# 3_2___TFT_IPS_320x480.net
KiCad netlist of a schematic drawn in Altium Designer
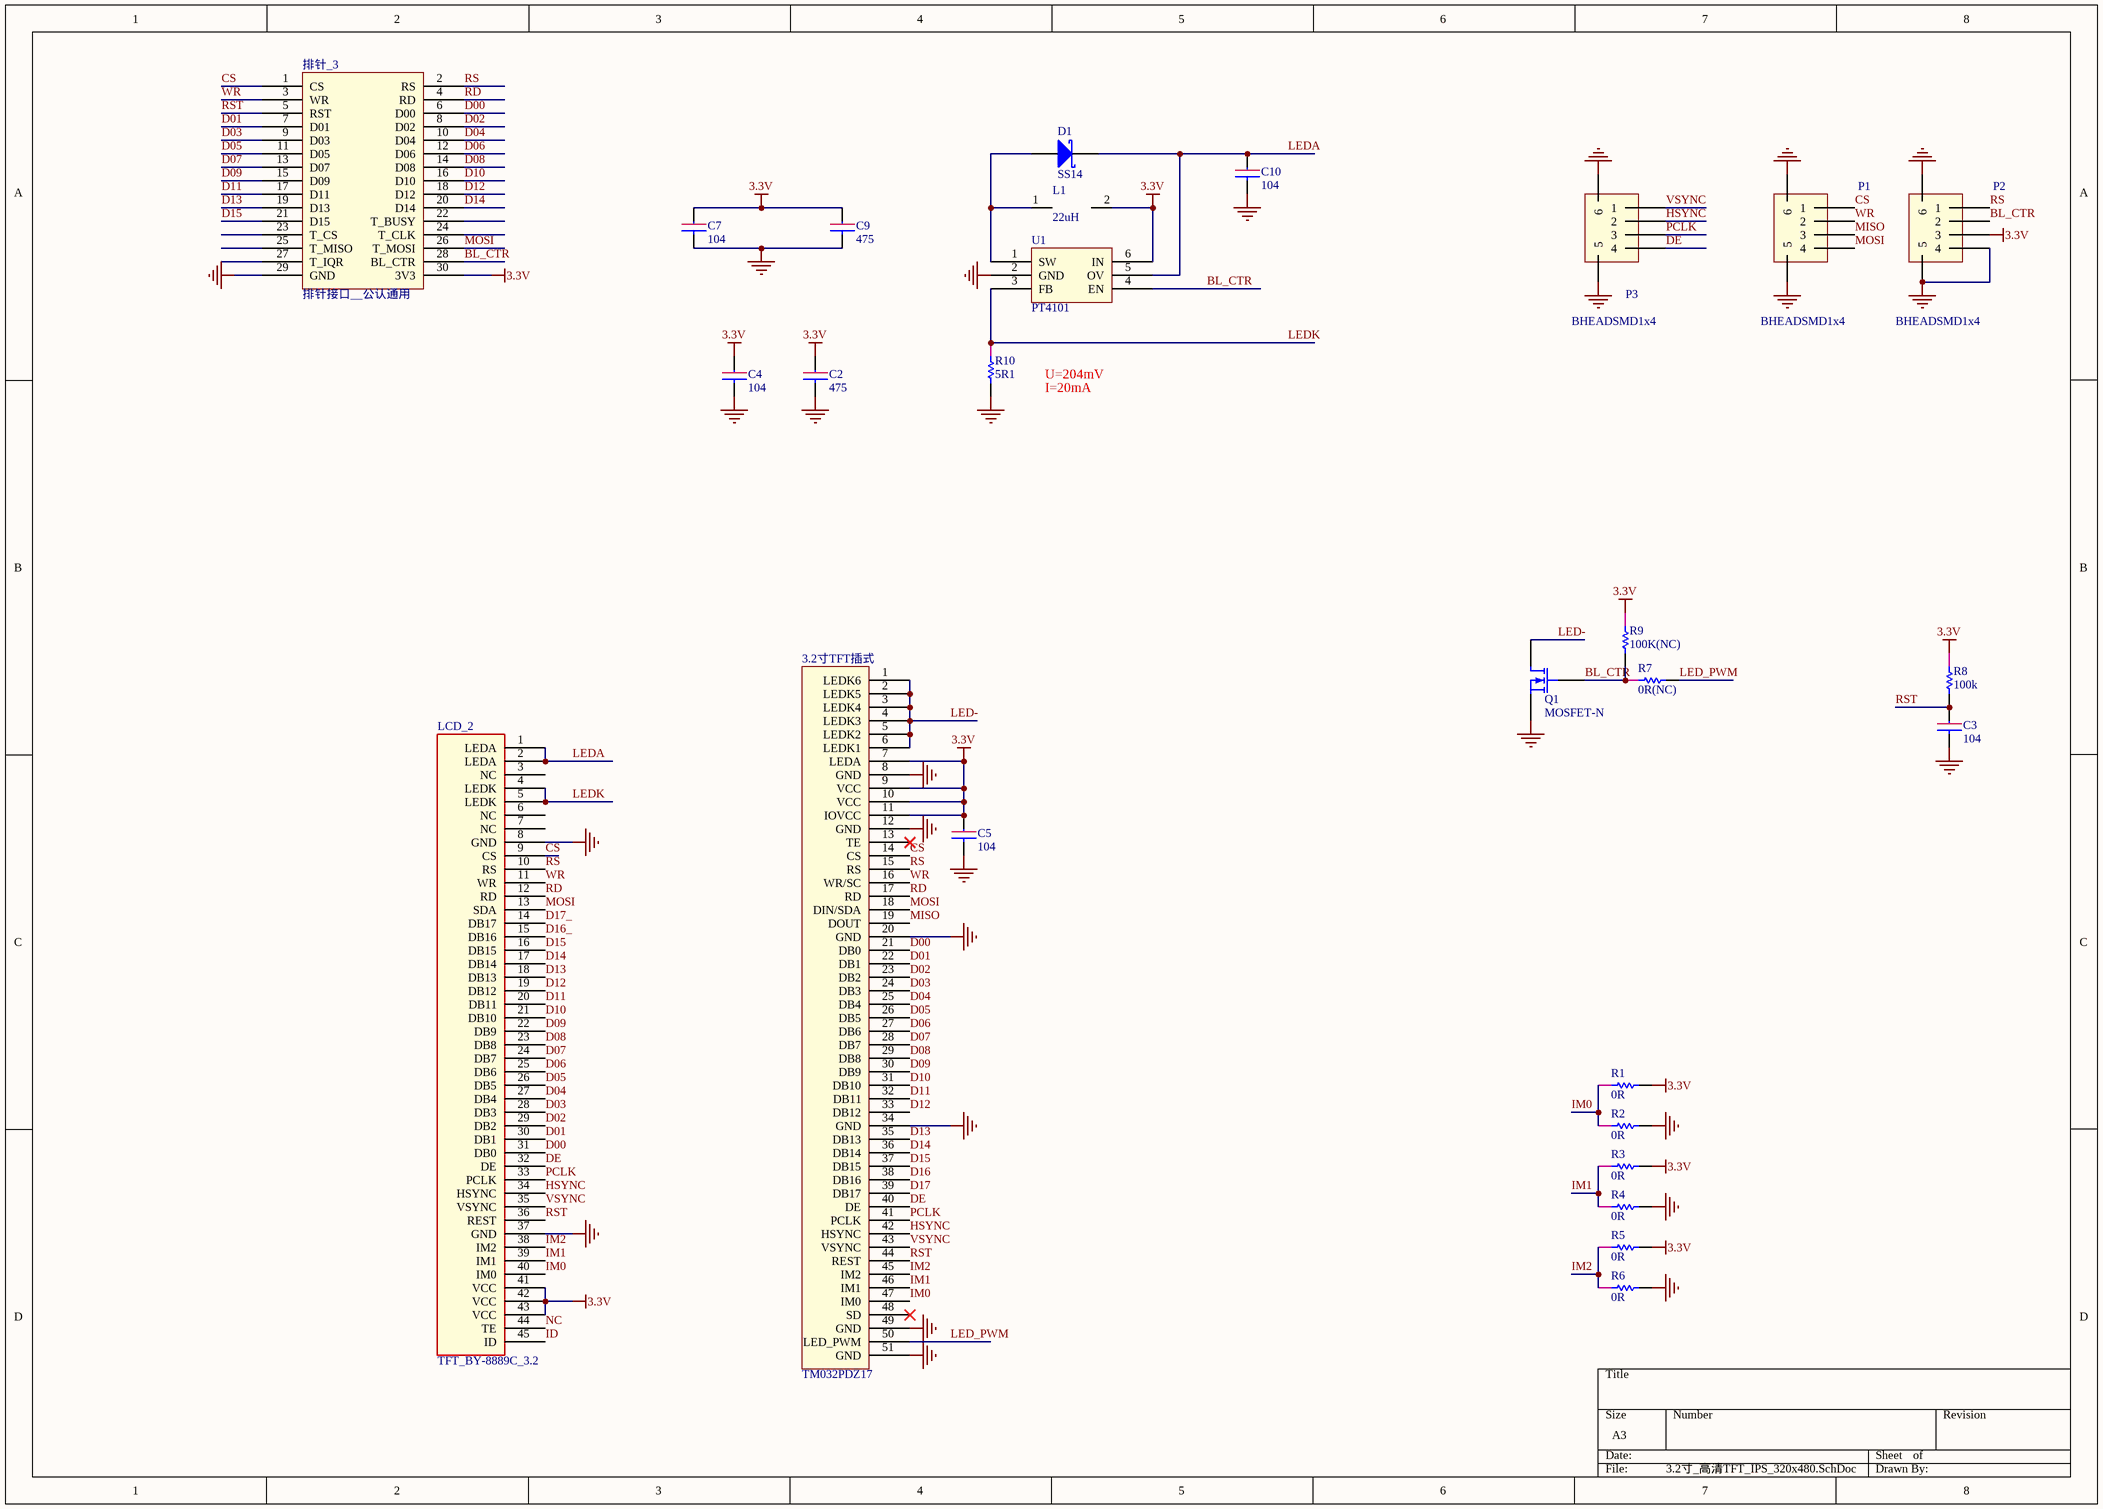
[diagram p0: 3.2寸_高清TFT_IPS_320x480.SchDoc]

(export (version "E")
  (design (tool "Eeschema 10.0.6"))
  (components
    (comp (ref "3.2寸TFT插式")
      (value "TM032PDZ17")
      (footprint "TM032PDZ17")
      (libsource (lib "Tiky") (part "TM032PDZ17"))
    )
    (comp (ref "C2") (value "475") (footprint "C0603-2") (libsource (lib "Tiky") (part "cap")))
    (comp (ref "C3") (value "104") (footprint "C0603-1") (libsource (lib "Tiky") (part "cap")))
    (comp (ref "C4") (value "104") (footprint "C0603-1") (libsource (lib "Tiky") (part "cap")))
    (comp (ref "C5") (value "104") (footprint "C0603-1") (libsource (lib "Tiky") (part "cap")))
    (comp (ref "C7") (value "104") (footprint "C0603-1") (libsource (lib "Tiky") (part "cap")))
    (comp (ref "C9") (value "475") (footprint "C0603-2") (libsource (lib "Tiky") (part "cap")))
    (comp (ref "C10") (value "104") (footprint "C0603-2") (libsource (lib "Tiky") (part "cap")))
    (comp (ref "D1")
      (value "SS14")
      (footprint "SOD123")
      (description "Schottky Diode")
      (fields (field (name "PUBLISHER") "Altium Limited"))
      (libsource (lib "Miscellaneous Devices") (part "D Schottky"))
    )
    (comp (ref "L1") (value "22uH") (footprint "L1206") (libsource (lib "Tiky") (part "Inductor")))
    (comp (ref "LCD_2")
      (value "TFT_BY-8889C_3.2")
      (footprint "TM032PDZ13")
      (libsource (lib "Tiky") (part "TFT_BY-8889C_3.2"))
    )
    (comp (ref "P1")
      (value "BHEADSMD1x4")
      (footprint "BHEADSMD1x4")
      (libsource (lib "Tiky") (part "BHEADSMD1x4"))
    )
    (comp (ref "P2")
      (value "BHEADSMD1x4")
      (footprint "BHEADSMD1x4")
      (libsource (lib "Tiky") (part "BHEADSMD1x4"))
    )
    (comp (ref "P3")
      (value "BHEADSMD1x4")
      (footprint "BHEADSMD1x4")
      (libsource (lib "Tiky") (part "BHEADSMD1x4"))
    )
    (comp (ref "Q1") (value "MOSFET-N") (footprint "SOT23A") (libsource (lib "Tiky") (part "MOSFET-N")))
    (comp (ref "R1") (value "0R") (footprint "R0603") (libsource (lib "Tiky") (part "Resistor")))
    (comp (ref "R2") (value "0R") (footprint "R0603") (libsource (lib "Tiky") (part "Resistor")))
    (comp (ref "R3") (value "0R") (footprint "R0603") (libsource (lib "Tiky") (part "Resistor")))
    (comp (ref "R4") (value "0R") (footprint "R0603") (libsource (lib "Tiky") (part "Resistor")))
    (comp (ref "R5") (value "0R") (footprint "R0603") (libsource (lib "Tiky") (part "Resistor")))
    (comp (ref "R6") (value "0R") (footprint "R0603") (libsource (lib "Tiky") (part "Resistor")))
    (comp (ref "R7") (value "0R(NC)") (footprint "R0603") (libsource (lib "Tiky") (part "Resistor")))
    (comp (ref "R8") (value "100k") (footprint "R0603") (libsource (lib "Tiky") (part "Resistor")))
    (comp (ref "R9") (value "100K(NC)") (footprint "R0603") (libsource (lib "Tiky") (part "Resistor")))
    (comp (ref "R10") (value "5R1") (footprint "R0603") (libsource (lib "Tiky") (part "Resistor")))
    (comp (ref "U1") (value "PT4101") (footprint "SOT23-6") (libsource (lib "Tiky") (part "PT4101")))
    (comp (ref "排针_3")
      (value "排针接口__公认通用")
      (footprint "P_Head_2x15")
      (libsource (lib "Tiky") (part "LCD_common"))
    )
  )
  (nets
    (net (code "1") (name "/BL_CTR") (class "Default")
      (node (ref "P2") (pin "2") (pinfunction "2_2") (pintype "passive"))
      (node (ref "Q1") (pin "1") (pinfunction "G_1") (pintype "passive"))
      (node (ref "R7") (pin "1") (pinfunction "1_1") (pintype "passive"))
      (node (ref "R9") (pin "2") (pinfunction "2_2") (pintype "passive"))
      (node (ref "U1") (pin "4") (pinfunction "EN_4") (pintype "passive"))
      (node (ref "排针_3") (pin "28") (pinfunction "BL_CTR_28") (pintype "passive"))
    )
    (net (code "2") (name "/CS") (class "Default")
      (node (ref "3.2寸TFT插式") (pin "14") (pinfunction "CS_14") (pintype "passive"))
      (node (ref "LCD_2") (pin "9") (pinfunction "CS_9") (pintype "passive"))
      (node (ref "P1") (pin "1") (pinfunction "1_1") (pintype "passive"))
      (node (ref "排针_3") (pin "1") (pinfunction "CS_1") (pintype "passive"))
    )
    (net (code "3") (name "/D00") (class "Default")
      (node (ref "3.2寸TFT插式") (pin "21") (pinfunction "DB0_21") (pintype "passive"))
      (node (ref "LCD_2") (pin "31") (pinfunction "DB0_31") (pintype "passive"))
      (node (ref "排针_3") (pin "6") (pinfunction "D00_6") (pintype "passive"))
    )
    (net (code "4") (name "/D01") (class "Default")
      (node (ref "3.2寸TFT插式") (pin "22") (pinfunction "DB1_22") (pintype "passive"))
      (node (ref "LCD_2") (pin "30") (pinfunction "DB1_30") (pintype "passive"))
      (node (ref "排针_3") (pin "7") (pinfunction "D01_7") (pintype "passive"))
    )
    (net (code "5") (name "/D02") (class "Default")
      (node (ref "3.2寸TFT插式") (pin "23") (pinfunction "DB2_23") (pintype "passive"))
      (node (ref "LCD_2") (pin "29") (pinfunction "DB2_29") (pintype "passive"))
      (node (ref "排针_3") (pin "8") (pinfunction "D02_8") (pintype "passive"))
    )
    (net (code "6") (name "/D03") (class "Default")
      (node (ref "3.2寸TFT插式") (pin "24") (pinfunction "DB3_24") (pintype "passive"))
      (node (ref "LCD_2") (pin "28") (pinfunction "DB3_28") (pintype "passive"))
      (node (ref "排针_3") (pin "9") (pinfunction "D03_9") (pintype "passive"))
    )
    (net (code "7") (name "/D04") (class "Default")
      (node (ref "3.2寸TFT插式") (pin "25") (pinfunction "DB4_25") (pintype "passive"))
      (node (ref "LCD_2") (pin "27") (pinfunction "DB4_27") (pintype "passive"))
      (node (ref "排针_3") (pin "10") (pinfunction "D04_10") (pintype "passive"))
    )
    (net (code "8") (name "/D05") (class "Default")
      (node (ref "3.2寸TFT插式") (pin "26") (pinfunction "DB5_26") (pintype "passive"))
      (node (ref "LCD_2") (pin "26") (pinfunction "DB5_26") (pintype "passive"))
      (node (ref "排针_3") (pin "11") (pinfunction "D05_11") (pintype "passive"))
    )
    (net (code "9") (name "/D06") (class "Default")
      (node (ref "3.2寸TFT插式") (pin "27") (pinfunction "DB6_27") (pintype "passive"))
      (node (ref "LCD_2") (pin "25") (pinfunction "DB6_25") (pintype "passive"))
      (node (ref "排针_3") (pin "12") (pinfunction "D06_12") (pintype "passive"))
    )
    (net (code "10") (name "/D07") (class "Default")
      (node (ref "3.2寸TFT插式") (pin "28") (pinfunction "DB7_28") (pintype "passive"))
      (node (ref "LCD_2") (pin "24") (pinfunction "DB7_24") (pintype "passive"))
      (node (ref "排针_3") (pin "13") (pinfunction "D07_13") (pintype "passive"))
    )
    (net (code "11") (name "/D08") (class "Default")
      (node (ref "3.2寸TFT插式") (pin "29") (pinfunction "DB8_29") (pintype "passive"))
      (node (ref "LCD_2") (pin "23") (pinfunction "DB8_23") (pintype "passive"))
      (node (ref "排针_3") (pin "14") (pinfunction "D08_14") (pintype "passive"))
    )
    (net (code "12") (name "/D09") (class "Default")
      (node (ref "3.2寸TFT插式") (pin "30") (pinfunction "DB9_30") (pintype "passive"))
      (node (ref "LCD_2") (pin "22") (pinfunction "DB9_22") (pintype "passive"))
      (node (ref "排针_3") (pin "15") (pinfunction "D09_15") (pintype "passive"))
    )
    (net (code "13") (name "/D10") (class "Default")
      (node (ref "3.2寸TFT插式") (pin "31") (pinfunction "DB10_31") (pintype "passive"))
      (node (ref "LCD_2") (pin "21") (pinfunction "DB10_21") (pintype "passive"))
      (node (ref "排针_3") (pin "16") (pinfunction "D10_16") (pintype "passive"))
    )
    (net (code "14") (name "/D11") (class "Default")
      (node (ref "3.2寸TFT插式") (pin "32") (pinfunction "DB11_32") (pintype "passive"))
      (node (ref "LCD_2") (pin "20") (pinfunction "DB11_20") (pintype "passive"))
      (node (ref "排针_3") (pin "17") (pinfunction "D11_17") (pintype "passive"))
    )
    (net (code "15") (name "/D12") (class "Default")
      (node (ref "3.2寸TFT插式") (pin "33") (pinfunction "DB12_33") (pintype "passive"))
      (node (ref "LCD_2") (pin "19") (pinfunction "DB12_19") (pintype "passive"))
      (node (ref "排针_3") (pin "18") (pinfunction "D12_18") (pintype "passive"))
    )
    (net (code "16") (name "/D13") (class "Default")
      (node (ref "3.2寸TFT插式") (pin "35") (pinfunction "DB13_35") (pintype "passive"))
      (node (ref "LCD_2") (pin "18") (pinfunction "DB13_18") (pintype "passive"))
      (node (ref "排针_3") (pin "19") (pinfunction "D13_19") (pintype "passive"))
    )
    (net (code "17") (name "/D14") (class "Default")
      (node (ref "3.2寸TFT插式") (pin "36") (pinfunction "DB14_36") (pintype "passive"))
      (node (ref "LCD_2") (pin "17") (pinfunction "DB14_17") (pintype "passive"))
      (node (ref "排针_3") (pin "20") (pinfunction "D14_20") (pintype "passive"))
    )
    (net (code "18") (name "/D15") (class "Default")
      (node (ref "3.2寸TFT插式") (pin "37") (pinfunction "DB15_37") (pintype "passive"))
      (node (ref "LCD_2") (pin "16") (pinfunction "DB15_16") (pintype "passive"))
      (node (ref "排针_3") (pin "21") (pinfunction "D15_21") (pintype "passive"))
    )
    (net (code "19") (name "/D16") (class "Default")
      (node (ref "3.2寸TFT插式") (pin "38") (pinfunction "DB16_38") (pintype "passive"))
    )
    (net (code "20") (name "/D16_") (class "Default")
      (node (ref "LCD_2") (pin "15") (pinfunction "DB16_15") (pintype "passive"))
    )
    (net (code "21") (name "/D17") (class "Default")
      (node (ref "3.2寸TFT插式") (pin "39") (pinfunction "DB17_39") (pintype "passive"))
    )
    (net (code "22") (name "/D17_") (class "Default")
      (node (ref "LCD_2") (pin "14") (pinfunction "DB17_14") (pintype "passive"))
    )
    (net (code "23") (name "/DE") (class "Default")
      (node (ref "3.2寸TFT插式") (pin "40") (pinfunction "DE_40") (pintype "passive"))
      (node (ref "LCD_2") (pin "32") (pinfunction "DE_32") (pintype "passive"))
      (node (ref "P3") (pin "4") (pinfunction "4_4") (pintype "passive"))
    )
    (net (code "24") (name "/HSYNC") (class "Default")
      (node (ref "3.2寸TFT插式") (pin "42") (pinfunction "HSYNC_42") (pintype "passive"))
      (node (ref "LCD_2") (pin "34") (pinfunction "HSYNC_34") (pintype "passive"))
      (node (ref "P3") (pin "2") (pinfunction "2_2") (pintype "passive"))
    )
    (net (code "25") (name "/ID") (class "Default")
      (node (ref "LCD_2") (pin "45") (pinfunction "ID_45") (pintype "passive"))
    )
    (net (code "26") (name "/IM0") (class "Default")
      (node (ref "3.2寸TFT插式") (pin "47") (pinfunction "IM0_47") (pintype "passive"))
      (node (ref "LCD_2") (pin "40") (pinfunction "IM0_40") (pintype "passive"))
      (node (ref "R1") (pin "1") (pinfunction "1_1") (pintype "passive"))
      (node (ref "R2") (pin "1") (pinfunction "1_1") (pintype "passive"))
    )
    (net (code "27") (name "/IM1") (class "Default")
      (node (ref "3.2寸TFT插式") (pin "46") (pinfunction "IM1_46") (pintype "passive"))
      (node (ref "LCD_2") (pin "39") (pinfunction "IM1_39") (pintype "passive"))
      (node (ref "R3") (pin "1") (pinfunction "1_1") (pintype "passive"))
      (node (ref "R4") (pin "1") (pinfunction "1_1") (pintype "passive"))
    )
    (net (code "28") (name "/IM2") (class "Default")
      (node (ref "3.2寸TFT插式") (pin "45") (pinfunction "IM2_45") (pintype "passive"))
      (node (ref "LCD_2") (pin "38") (pinfunction "IM2_38") (pintype "passive"))
      (node (ref "R5") (pin "1") (pinfunction "1_1") (pintype "passive"))
      (node (ref "R6") (pin "1") (pinfunction "1_1") (pintype "passive"))
    )
    (net (code "29") (name "/LED-") (class "Default")
      (node (ref "3.2寸TFT插式") (pin "1") (pinfunction "LEDK6_1") (pintype "passive"))
      (node (ref "3.2寸TFT插式") (pin "2") (pinfunction "LEDK5_2") (pintype "passive"))
      (node (ref "3.2寸TFT插式") (pin "3") (pinfunction "LEDK4_3") (pintype "passive"))
      (node (ref "3.2寸TFT插式") (pin "4") (pinfunction "LEDK3_4") (pintype "passive"))
      (node (ref "3.2寸TFT插式") (pin "5") (pinfunction "LEDK2_5") (pintype "passive"))
      (node (ref "3.2寸TFT插式") (pin "6") (pinfunction "LEDK1_6") (pintype "passive"))
      (node (ref "Q1") (pin "3") (pinfunction "D_3") (pintype "passive"))
    )
    (net (code "30") (name "/LEDA") (class "Default")
      (node (ref "C10") (pin "1") (pinfunction "1_1") (pintype "passive"))
      (node (ref "D1") (pin "2") (pinfunction "K_2") (pintype "passive"))
      (node (ref "LCD_2") (pin "1") (pinfunction "LEDA_1") (pintype "passive"))
      (node (ref "LCD_2") (pin "2") (pinfunction "LEDA_2") (pintype "passive"))
      (node (ref "U1") (pin "5") (pinfunction "OV_5") (pintype "passive"))
    )
    (net (code "31") (name "/LEDK") (class "Default")
      (node (ref "LCD_2") (pin "4") (pinfunction "LEDK_4") (pintype "passive"))
      (node (ref "LCD_2") (pin "5") (pinfunction "LEDK_5") (pintype "passive"))
      (node (ref "R10") (pin "1") (pinfunction "1_1") (pintype "passive"))
      (node (ref "U1") (pin "3") (pinfunction "FB_3") (pintype "passive"))
    )
    (net (code "32") (name "/LED_PWM") (class "Default")
      (node (ref "3.2寸TFT插式") (pin "50") (pinfunction "LED_PWM_50") (pintype "passive"))
      (node (ref "R7") (pin "2") (pinfunction "2_2") (pintype "passive"))
    )
    (net (code "33") (name "/MISO") (class "Default")
      (node (ref "3.2寸TFT插式") (pin "19") (pinfunction "DOUT_19") (pintype "passive"))
      (node (ref "P1") (pin "3") (pinfunction "3_3") (pintype "passive"))
    )
    (net (code "34") (name "/MOSI") (class "Default")
      (node (ref "3.2寸TFT插式") (pin "18") (pinfunction "DIN/SDA_18") (pintype "passive"))
      (node (ref "LCD_2") (pin "13") (pinfunction "SDA_13") (pintype "passive"))
      (node (ref "P1") (pin "4") (pinfunction "4_4") (pintype "passive"))
      (node (ref "排针_3") (pin "26") (pinfunction "T_MOSI_26") (pintype "passive"))
    )
    (net (code "35") (name "/NC") (class "Default")
      (node (ref "LCD_2") (pin "44") (pinfunction "TE_44") (pintype "passive"))
    )
    (net (code "36") (name "/PCLK") (class "Default")
      (node (ref "3.2寸TFT插式") (pin "41") (pinfunction "PCLK_41") (pintype "passive"))
      (node (ref "LCD_2") (pin "33") (pinfunction "PCLK_33") (pintype "passive"))
      (node (ref "P3") (pin "3") (pinfunction "3_3") (pintype "passive"))
    )
    (net (code "37") (name "/RD") (class "Default")
      (node (ref "3.2寸TFT插式") (pin "17") (pinfunction "RD_17") (pintype "passive"))
      (node (ref "LCD_2") (pin "12") (pinfunction "RD_12") (pintype "passive"))
      (node (ref "排针_3") (pin "4") (pinfunction "RD_4") (pintype "passive"))
    )
    (net (code "38") (name "/RS") (class "Default")
      (node (ref "3.2寸TFT插式") (pin "15") (pinfunction "RS_15") (pintype "passive"))
      (node (ref "LCD_2") (pin "10") (pinfunction "RS_10") (pintype "passive"))
      (node (ref "P2") (pin "1") (pinfunction "1_1") (pintype "passive"))
      (node (ref "排针_3") (pin "2") (pinfunction "RS_2") (pintype "passive"))
    )
    (net (code "39") (name "/RST") (class "Default")
      (node (ref "3.2寸TFT插式") (pin "44") (pinfunction "REST_44") (pintype "passive"))
      (node (ref "C3") (pin "1") (pinfunction "1_1") (pintype "passive"))
      (node (ref "LCD_2") (pin "36") (pinfunction "REST_36") (pintype "passive"))
      (node (ref "R8") (pin "2") (pinfunction "2_2") (pintype "passive"))
      (node (ref "排针_3") (pin "5") (pinfunction "RST_5") (pintype "passive"))
    )
    (net (code "40") (name "/VSYNC") (class "Default")
      (node (ref "3.2寸TFT插式") (pin "43") (pinfunction "VSYNC_43") (pintype "passive"))
      (node (ref "LCD_2") (pin "35") (pinfunction "VSYNC_35") (pintype "passive"))
      (node (ref "P3") (pin "1") (pinfunction "1_1") (pintype "passive"))
    )
    (net (code "41") (name "/WR") (class "Default")
      (node (ref "3.2寸TFT插式") (pin "16") (pinfunction "WR/SC_16") (pintype "passive"))
      (node (ref "LCD_2") (pin "11") (pinfunction "WR_11") (pintype "passive"))
      (node (ref "P1") (pin "2") (pinfunction "2_2") (pintype "passive"))
      (node (ref "排针_3") (pin "3") (pinfunction "WR_3") (pintype "passive"))
    )
    (net (code "42") (name "3.3V") (class "Default")
      (node (ref "3.2寸TFT插式") (pin "10") (pinfunction "VCC_10") (pintype "passive"))
      (node (ref "3.2寸TFT插式") (pin "11") (pinfunction "IOVCC_11") (pintype "passive"))
      (node (ref "3.2寸TFT插式") (pin "7") (pinfunction "LEDA_7") (pintype "passive"))
      (node (ref "3.2寸TFT插式") (pin "9") (pinfunction "VCC_9") (pintype "passive"))
      (node (ref "C2") (pin "1") (pinfunction "1_1") (pintype "passive"))
      (node (ref "C4") (pin "1") (pinfunction "1_1") (pintype "passive"))
      (node (ref "C5") (pin "1") (pinfunction "1_1") (pintype "passive"))
      (node (ref "C7") (pin "1") (pinfunction "1_1") (pintype "passive"))
      (node (ref "C9") (pin "1") (pinfunction "1_1") (pintype "passive"))
      (node (ref "L1") (pin "2") (pinfunction "2_2") (pintype "passive"))
      (node (ref "LCD_2") (pin "41") (pinfunction "VCC_41") (pintype "passive"))
      (node (ref "LCD_2") (pin "42") (pinfunction "VCC_42") (pintype "passive"))
      (node (ref "LCD_2") (pin "43") (pinfunction "VCC_43") (pintype "passive"))
      (node (ref "P2") (pin "3") (pinfunction "3_3") (pintype "passive"))
      (node (ref "R1") (pin "2") (pinfunction "2_2") (pintype "passive"))
      (node (ref "R3") (pin "2") (pinfunction "2_2") (pintype "passive"))
      (node (ref "R5") (pin "2") (pinfunction "2_2") (pintype "passive"))
      (node (ref "R8") (pin "1") (pinfunction "1_1") (pintype "passive"))
      (node (ref "R9") (pin "1") (pinfunction "1_1") (pintype "passive"))
      (node (ref "U1") (pin "6") (pinfunction "IN_6") (pintype "passive"))
      (node (ref "排针_3") (pin "30") (pinfunction "3V3_30") (pintype "passive"))
    )
    (net (code "43") (name "GND") (class "Default")
      (node (ref "3.2寸TFT插式") (pin "12") (pinfunction "GND_12") (pintype "passive"))
      (node (ref "3.2寸TFT插式") (pin "20") (pinfunction "GND_20") (pintype "passive"))
      (node (ref "3.2寸TFT插式") (pin "34") (pinfunction "GND_34") (pintype "passive"))
      (node (ref "3.2寸TFT插式") (pin "49") (pinfunction "GND_49") (pintype "passive"))
      (node (ref "3.2寸TFT插式") (pin "51") (pinfunction "GND_51") (pintype "passive"))
      (node (ref "3.2寸TFT插式") (pin "8") (pinfunction "GND_8") (pintype "passive"))
      (node (ref "C10") (pin "2") (pinfunction "2_2") (pintype "passive"))
      (node (ref "C2") (pin "2") (pinfunction "2_2") (pintype "passive"))
      (node (ref "C3") (pin "2") (pinfunction "2_2") (pintype "passive"))
      (node (ref "C4") (pin "2") (pinfunction "2_2") (pintype "passive"))
      (node (ref "C5") (pin "2") (pinfunction "2_2") (pintype "passive"))
      (node (ref "C7") (pin "2") (pinfunction "2_2") (pintype "passive"))
      (node (ref "C9") (pin "2") (pinfunction "2_2") (pintype "passive"))
      (node (ref "LCD_2") (pin "37") (pinfunction "GND_37") (pintype "passive"))
      (node (ref "LCD_2") (pin "8") (pinfunction "GND_8") (pintype "passive"))
      (node (ref "P1") (pin "5") (pinfunction "5_5") (pintype "passive"))
      (node (ref "P1") (pin "6") (pinfunction "6_6") (pintype "passive"))
      (node (ref "P2") (pin "4") (pinfunction "4_4") (pintype "passive"))
      (node (ref "P2") (pin "5") (pinfunction "5_5") (pintype "passive"))
      (node (ref "P2") (pin "6") (pinfunction "6_6") (pintype "passive"))
      (node (ref "P3") (pin "5") (pinfunction "5_5") (pintype "passive"))
      (node (ref "P3") (pin "6") (pinfunction "6_6") (pintype "passive"))
      (node (ref "Q1") (pin "2") (pinfunction "S_2") (pintype "passive"))
      (node (ref "R10") (pin "2") (pinfunction "2_2") (pintype "passive"))
      (node (ref "R2") (pin "2") (pinfunction "2_2") (pintype "passive"))
      (node (ref "R4") (pin "2") (pinfunction "2_2") (pintype "passive"))
      (node (ref "R6") (pin "2") (pinfunction "2_2") (pintype "passive"))
      (node (ref "U1") (pin "2") (pinfunction "GND_2") (pintype "passive"))
      (node (ref "排针_3") (pin "29") (pinfunction "GND_29") (pintype "passive"))
    )
    (net (code "44") (name "Net-(D1-A)") (class "Default")
      (node (ref "D1") (pin "1") (pinfunction "A_1") (pintype "passive"))
      (node (ref "L1") (pin "1") (pinfunction "1_1") (pintype "passive"))
      (node (ref "U1") (pin "1") (pinfunction "SW_1") (pintype "passive"))
    )
    (net (code "45") (name "unconnected-(3.2寸TFT插式-SD-Pad48)") (class "Default")
      (node (ref "3.2寸TFT插式") (pin "48") (pinfunction "SD_48") (pintype "passive+no_connect"))
    )
    (net (code "46") (name "unconnected-(3.2寸TFT插式-TE-Pad13)") (class "Default")
      (node (ref "3.2寸TFT插式") (pin "13") (pinfunction "TE_13") (pintype "passive+no_connect"))
    )
    (net (code "47") (name "unconnected-(LCD_2-NC-Pad3)") (class "Default")
      (node (ref "LCD_2") (pin "3") (pinfunction "NC_3") (pintype "passive"))
    )
    (net (code "48") (name "unconnected-(LCD_2-NC-Pad6)") (class "Default")
      (node (ref "LCD_2") (pin "6") (pinfunction "NC_6") (pintype "passive"))
    )
    (net (code "49") (name "unconnected-(LCD_2-NC-Pad7)") (class "Default")
      (node (ref "LCD_2") (pin "7") (pinfunction "NC_7") (pintype "passive"))
    )
    (net (code "50") (name "unconnected-(排针_3-T_BUSY-Pad22)") (class "Default")
      (node (ref "排针_3") (pin "22") (pinfunction "T_BUSY_22") (pintype "passive"))
    )
    (net (code "51") (name "unconnected-(排针_3-T_CLK-Pad24)") (class "Default")
      (node (ref "排针_3") (pin "24") (pinfunction "T_CLK_24") (pintype "passive"))
    )
    (net (code "52") (name "unconnected-(排针_3-T_CS-Pad23)") (class "Default")
      (node (ref "排针_3") (pin "23") (pinfunction "T_CS_23") (pintype "passive"))
    )
    (net (code "53") (name "unconnected-(排针_3-T_IQR-Pad27)") (class "Default")
      (node (ref "排针_3") (pin "27") (pinfunction "T_IQR_27") (pintype "passive"))
    )
    (net (code "54") (name "unconnected-(排针_3-T_MISO-Pad25)") (class "Default")
      (node (ref "排针_3") (pin "25") (pinfunction "T_MISO_25") (pintype "passive"))
    )
  )
)
